# RGB_LED.net
KiCad netlist of a schematic drawn in Altium Designer
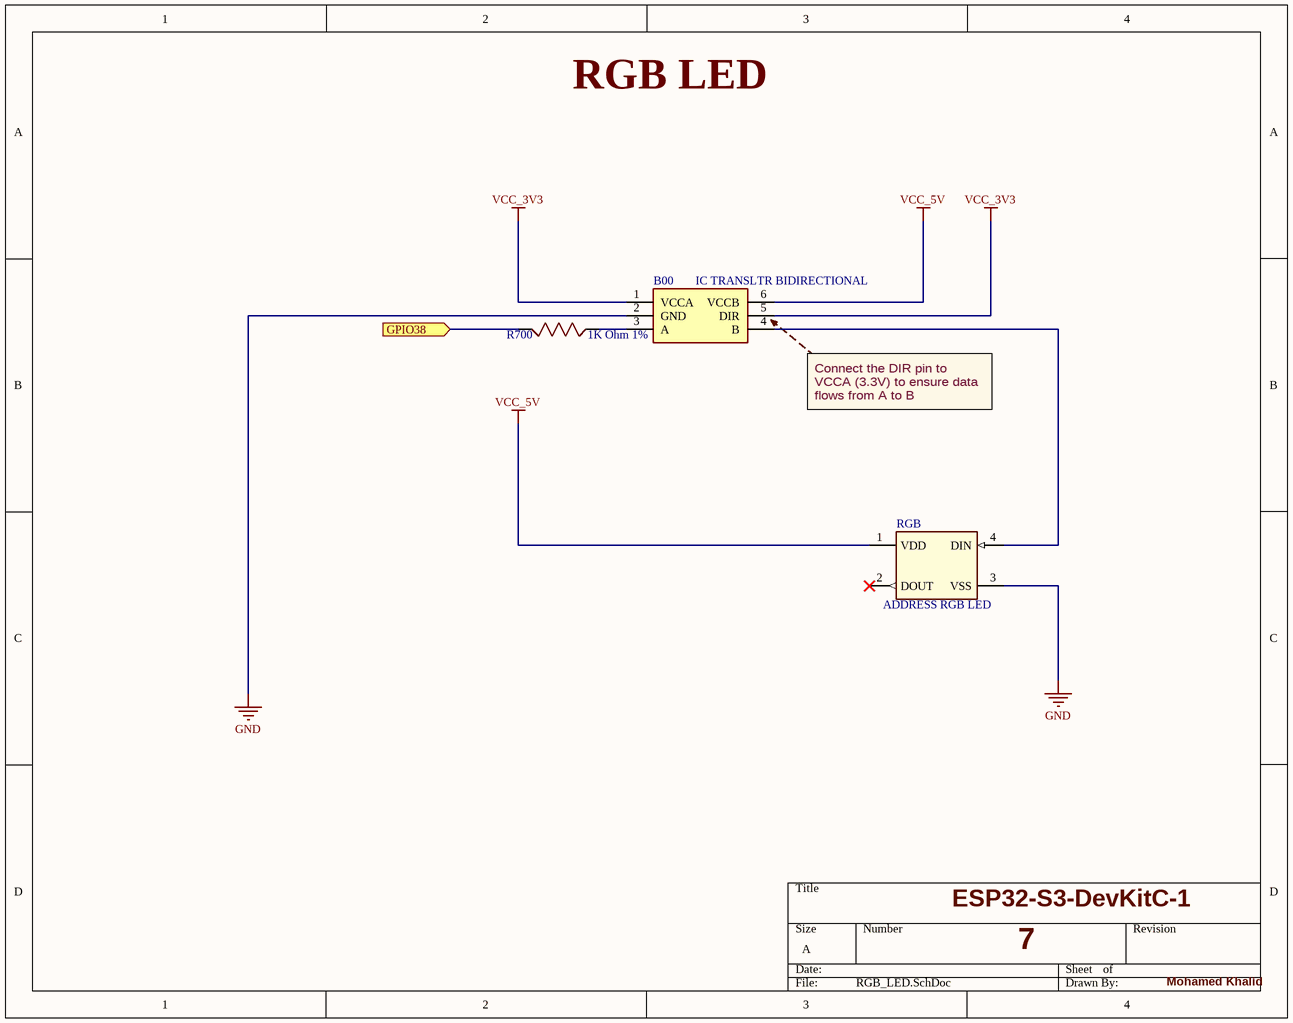
[diagram p0: RGB_LED.SchDoc]

(export (version "E")
  (design (tool "Eeschema 10.0.6"))
  (components
    (comp (ref "B00")
      (value "IC TRANSLTR BIDIRECTIONAL")
      (footprint "SOTFL50P160X60-6N")
      (description "Voltage Level Translator Bidirectional 1 Circuit 1 Channel 420Mbps SOT-5X3")
      (libsource (lib "ESP32_Integrated_Library") (part "SN74LVC1T45DRLR"))
    )
    (comp (ref "R700")
      (value "1K Ohm 1%")
      (footprint "RESC2012X65N")
      (description "1 kOhms ±1% 0.125W, 1/8W Chip Resistor 0805 (2012 Metric) Automotive AEC-Q200 Thick Film")
      (fields (field (name "TOLERANCE") "± 1%"))
      (libsource (lib "ESP32_Integrated_Library") (part "RMCF0805FT1K00"))
    )
    (comp (ref "RGB")
      (value "ADDRESS RGB LED")
      (footprint "COM-16347_SPK")
      (description "Addressable Lighting - LED Serial NRZ (Shift Register) Red, Green, Blue (RGB) 5.00mm L x 5.00mm W")
      (libsource (lib "ESP32_Integrated_Library") (part "COM-16347"))
    )
  )
  (nets
    (net (code "1") (name "/GPIO38") (class "Default")
      (node (ref "R700") (pin "1") (pinfunction "1_1") (pintype "passive"))
    )
    (net (code "2") (name "GND") (class "Default")
      (node (ref "B00") (pin "2") (pinfunction "GND_2") (pintype "passive"))
      (node (ref "RGB") (pin "3") (pinfunction "VSS_3") (pintype "passive"))
    )
    (net (code "3") (name "Net-(B00-A)") (class "Default")
      (node (ref "B00") (pin "3") (pinfunction "A_3") (pintype "passive"))
      (node (ref "R700") (pin "2") (pinfunction "2_2") (pintype "passive"))
    )
    (net (code "4") (name "Net-(B00-B)") (class "Default")
      (node (ref "B00") (pin "4") (pinfunction "B_4") (pintype "passive"))
      (node (ref "RGB") (pin "4") (pinfunction "DIN_4") (pintype "input"))
    )
    (net (code "5") (name "VCC_3V3") (class "Default")
      (node (ref "B00") (pin "1") (pinfunction "VCCA_1") (pintype "passive"))
      (node (ref "B00") (pin "5") (pinfunction "DIR_5") (pintype "passive"))
    )
    (net (code "6") (name "VCC_5V") (class "Default")
      (node (ref "B00") (pin "6") (pinfunction "VCCB_6") (pintype "passive"))
      (node (ref "RGB") (pin "1") (pinfunction "VDD_1") (pintype "power_in"))
    )
    (net (code "7") (name "unconnected-(RGB-DOUT-Pad2)") (class "Default")
      (node (ref "RGB") (pin "2") (pinfunction "DOUT_2") (pintype "output+no_connect"))
    )
  )
)
